# BP_MCU.net
KiCad netlist of a schematic drawn in EAGLE
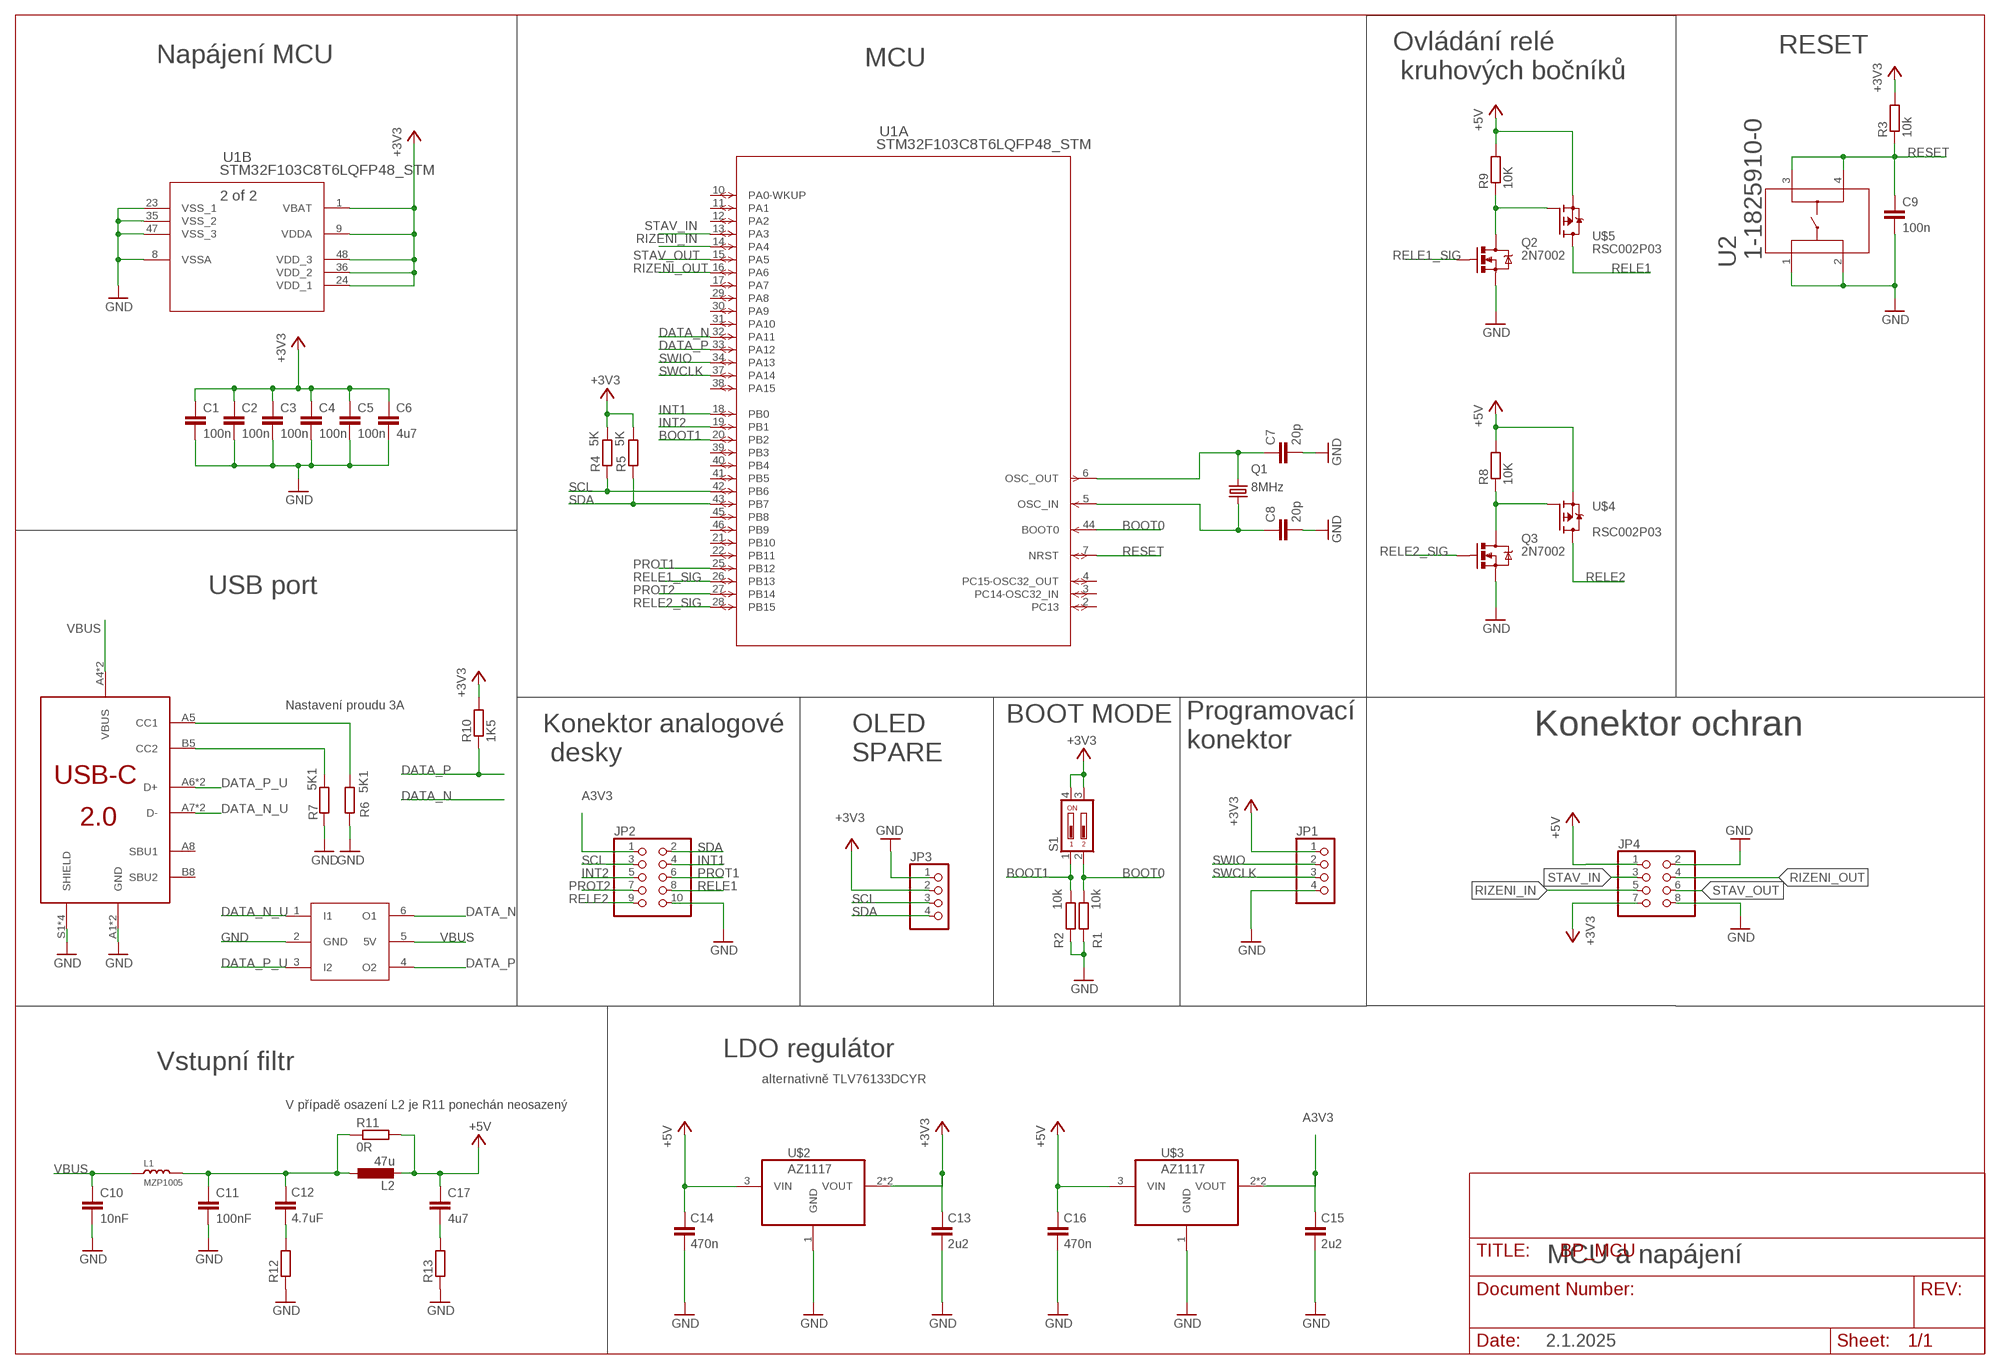
[diagram p0: schematic, sheet 1]

(export (version "E")
  (design (tool "Eeschema 10.0.6"))
  (components
    (comp (ref "C1")
      (value "100n")
      (footprint "eagle-import:C0805")
      (libsource (lib "eagle-import") (part "C-EUC0805"))
    )
    (comp (ref "C2")
      (value "100n")
      (footprint "eagle-import:C0805")
      (libsource (lib "eagle-import") (part "C-EUC0805"))
    )
    (comp (ref "C3")
      (value "100n")
      (footprint "eagle-import:C0805")
      (libsource (lib "eagle-import") (part "C-EUC0805"))
    )
    (comp (ref "C4")
      (value "100n")
      (footprint "eagle-import:C0805")
      (libsource (lib "eagle-import") (part "C-EUC0805"))
    )
    (comp (ref "C5")
      (value "100n")
      (footprint "eagle-import:C0805")
      (libsource (lib "eagle-import") (part "C-EUC0805"))
    )
    (comp (ref "C6")
      (value "4u7")
      (footprint "eagle-import:C0805")
      (libsource (lib "eagle-import") (part "C-EUC0805"))
    )
    (comp (ref "C7")
      (value "20p")
      (footprint "eagle-import:C0805")
      (libsource (lib "eagle-import") (part "C-EUC0805"))
    )
    (comp (ref "C8")
      (value "20p")
      (footprint "eagle-import:C0805")
      (libsource (lib "eagle-import") (part "C-EUC0805"))
    )
    (comp (ref "C9")
      (value "100n")
      (footprint "eagle-import:C0805")
      (libsource (lib "eagle-import") (part "C-EUC0805"))
    )
    (comp (ref "C10")
      (value "10nF")
      (footprint "eagle-import:C0805")
      (libsource (lib "eagle-import") (part "C-EUC0805"))
    )
    (comp (ref "C11")
      (value "100nF")
      (footprint "eagle-import:C0805")
      (libsource (lib "eagle-import") (part "resistor_348_C-EUC0805"))
    )
    (comp (ref "C12")
      (value "4.7uF")
      (footprint "eagle-import:C0805")
      (libsource (lib "eagle-import") (part "resistor_348_C-EUC0805"))
    )
    (comp (ref "C13")
      (value "2u2")
      (footprint "eagle-import:C0805")
      (libsource (lib "eagle-import") (part "C-EUC0805"))
    )
    (comp (ref "C14")
      (value "470n")
      (footprint "eagle-import:C0805")
      (libsource (lib "eagle-import") (part "C-EUC0805"))
    )
    (comp (ref "C15")
      (value "2u2")
      (footprint "eagle-import:C0805")
      (libsource (lib "eagle-import") (part "C-EUC0805"))
    )
    (comp (ref "C16")
      (value "470n")
      (footprint "eagle-import:C0805")
      (libsource (lib "eagle-import") (part "C-EUC0805"))
    )
    (comp (ref "C17")
      (value "4u7")
      (footprint "eagle-import:C0805")
      (libsource (lib "eagle-import") (part "C-EUC0805"))
    )
    (comp (ref "JP1")
      (value "PINHD-1X4")
      (footprint "eagle-import:1X04")
      (libsource (lib "eagle-import") (part "PINHD-1X4"))
    )
    (comp (ref "JP2")
      (value "PINHD-2X5")
      (footprint "eagle-import:2X05")
      (libsource (lib "eagle-import") (part "PINHD-2X5"))
    )
    (comp (ref "JP3")
      (value "PINHD-1X4")
      (footprint "eagle-import:1X04")
      (libsource (lib "eagle-import") (part "PINHD-1X4"))
    )
    (comp (ref "JP4")
      (value "PINHD-2X4")
      (footprint "eagle-import:2X04")
      (libsource (lib "eagle-import") (part "PINHD-2X4"))
    )
    (comp (ref "L1")
      (value "MZP1005")
      (footprint "eagle-import:INDUCTOR_L0402")
      (libsource (lib "eagle-import") (part "INDUCTOR_INDUCTOR/FERRITE-BEAD0402"))
    )
    (comp (ref "L2")
      (value "47u")
      (footprint "eagle-import:AMRM001")
      (libsource (lib "eagle-import") (part "AMRM00101040470MA1"))
    )
    (comp (ref "Q1")
      (value "8MHz")
      (footprint "eagle-import:HC49UP")
      (libsource (lib "eagle-import") (part "CRYSTALHC49UP"))
    )
    (comp (ref "Q2")
      (value "2N7002")
      (footprint "eagle-import:SOT323")
      (libsource (lib "eagle-import") (part "MOSFET-NCHANNEL2N7002PW"))
    )
    (comp (ref "Q3")
      (value "2N7002")
      (footprint "eagle-import:SOT323")
      (libsource (lib "eagle-import") (part "MOSFET-NCHANNEL2N7002PW"))
    )
    (comp (ref "R1")
      (value "10k")
      (footprint "eagle-import:R0805")
      (libsource (lib "eagle-import") (part "R-EU_R0805"))
    )
    (comp (ref "R2")
      (value "10k")
      (footprint "eagle-import:R0805")
      (libsource (lib "eagle-import") (part "R-EU_R0805"))
    )
    (comp (ref "R3")
      (value "10k")
      (footprint "eagle-import:R0805")
      (libsource (lib "eagle-import") (part "R-EU_R0805"))
    )
    (comp (ref "R4")
      (value "5K")
      (footprint "eagle-import:R0805")
      (libsource (lib "eagle-import") (part "R-EU_R0805"))
    )
    (comp (ref "R5")
      (value "5K")
      (footprint "eagle-import:R0805")
      (libsource (lib "eagle-import") (part "R-EU_R0805"))
    )
    (comp (ref "R6")
      (value "5K1")
      (footprint "eagle-import:R0805")
      (libsource (lib "eagle-import") (part "R-EU_R0805"))
    )
    (comp (ref "R7")
      (value "5K1")
      (footprint "eagle-import:R0805")
      (libsource (lib "eagle-import") (part "R-EU_R0805"))
    )
    (comp (ref "R8")
      (value "10K")
      (footprint "eagle-import:R0805")
      (libsource (lib "eagle-import") (part "R-EU_R0805"))
    )
    (comp (ref "R9")
      (value "10K")
      (footprint "eagle-import:R0805")
      (libsource (lib "eagle-import") (part "R-EU_R0805"))
    )
    (comp (ref "R10")
      (value "1K5")
      (footprint "eagle-import:R0805")
      (libsource (lib "eagle-import") (part "R-EU_R0805"))
    )
    (comp (ref "R11")
      (value "0R")
      (footprint "eagle-import:R0805")
      (libsource (lib "eagle-import") (part "R-EU_R0805"))
    )
    (comp (ref "R12")
      (value "R-EU_R0805")
      (footprint "eagle-import:R0805")
      (libsource (lib "eagle-import") (part "R-EU_R0805"))
    )
    (comp (ref "R13")
      (value "R-EU_R0805")
      (footprint "eagle-import:R0805")
      (libsource (lib "eagle-import") (part "R-EU_R0805"))
    )
    (comp (ref "S1")
      (value "SD4-02")
      (footprint "eagle-import:SD4-02")
      (libsource (lib "eagle-import") (part "SD4-02"))
    )
    (comp (ref "U$1")
      (value "217179-0001-USB-C")
      (footprint "eagle-import:TYPEC16")
      (libsource (lib "eagle-import") (part "217179-0001-USB-C"))
    )
    (comp (ref "U$2")
      (value "AZ1117")
      (footprint "eagle-import:SOT230P700X180-4N")
      (libsource (lib "eagle-import") (part "AZ1117"))
    )
    (comp (ref "U$3")
      (value "AZ1117")
      (footprint "eagle-import:SOT230P700X180-4N")
      (libsource (lib "eagle-import") (part "AZ1117"))
    )
    (comp (ref "U$4")
      (value "RSC002P03")
      (footprint "eagle-import:SOT95")
      (libsource (lib "eagle-import") (part "RSC002P03"))
    )
    (comp (ref "U$5")
      (value "RSC002P03")
      (footprint "eagle-import:SOT95")
      (libsource (lib "eagle-import") (part "RSC002P03"))
    )
    (comp (ref "U$6")
      (value "USBLC6-2")
      (footprint "eagle-import:SOT23-6L")
      (libsource (lib "eagle-import") (part "USBLC6-2"))
    )
    (comp (ref "U1")
      (value "STM32F103C8T6LQFP48_STM")
      (footprint "eagle-import:LQFP48_STM")
      (fields
        (field (name "MANUFACTURER_PART_NUMBER") "STM32F103C8T6")
        (field (name "COPYRIGHT") "Copyright (C) 2024 Ultra Librarian. All rights reserved.")
      )
      (libsource (lib "eagle-import") (part "STM32F103C8T6LQFP48_STM"))
    )
    (comp (ref "U2")
      (value "1-1825910-0")
      (footprint "eagle-import:SWITCH_1-1825910-0")
      (fields (field (name "COPYRIGHT") "Copyright (C) 2016 Accelerated Designs. All rights reserved"))
      (libsource (lib "eagle-import") (part "1-1825910-0"))
    )
  )
  (nets
    (net (code "1") (name "+3V3") (class "Default")
      (node (ref "C1") (pin "1") (pinfunction "1_1") (pintype "passive"))
      (node (ref "C13") (pin "1") (pinfunction "1_1") (pintype "passive"))
      (node (ref "C2") (pin "1") (pinfunction "1_1") (pintype "passive"))
      (node (ref "C3") (pin "1") (pinfunction "1_1") (pintype "passive"))
      (node (ref "C4") (pin "1") (pinfunction "1_1") (pintype "passive"))
      (node (ref "C5") (pin "1") (pinfunction "1_1") (pintype "passive"))
      (node (ref "C6") (pin "1") (pinfunction "1_1") (pintype "passive"))
      (node (ref "JP1") (pin "1") (pinfunction "1_1") (pintype "passive"))
      (node (ref "JP3") (pin "2") (pinfunction "2_2") (pintype "passive"))
      (node (ref "JP4") (pin "7") (pinfunction "7_7") (pintype "passive"))
      (node (ref "R10") (pin "2") (pinfunction "2_2") (pintype "passive"))
      (node (ref "R3") (pin "2") (pinfunction "2_2") (pintype "passive"))
      (node (ref "R4") (pin "2") (pinfunction "2_2") (pintype "passive"))
      (node (ref "R5") (pin "2") (pinfunction "2_2") (pintype "passive"))
      (node (ref "S1") (pin "3") (pinfunction "3_3") (pintype "passive"))
      (node (ref "S1") (pin "4") (pinfunction "4_4") (pintype "passive"))
      (node (ref "U$2") (pin "2") (pinfunction "VOUT_2") (pintype "output"))
      (node (ref "U$2") (pin "4") (pinfunction "VOUT_4") (pintype "output"))
      (node (ref "U1") (pin "1") (pinfunction "VBAT_1") (pintype "power_in"))
      (node (ref "U1") (pin "24") (pinfunction "VDD_1_24") (pintype "power_in"))
      (node (ref "U1") (pin "36") (pinfunction "VDD_2_36") (pintype "power_in"))
      (node (ref "U1") (pin "48") (pinfunction "VDD_3_48") (pintype "power_in"))
      (node (ref "U1") (pin "9") (pinfunction "VDDA_9") (pintype "power_in"))
    )
    (net (code "2") (name "+5V") (class "Default")
      (node (ref "C14") (pin "1") (pinfunction "1_1") (pintype "passive"))
      (node (ref "C16") (pin "1") (pinfunction "1_1") (pintype "passive"))
      (node (ref "C17") (pin "1") (pinfunction "1_1") (pintype "passive"))
      (node (ref "JP4") (pin "1") (pinfunction "1_1") (pintype "passive"))
      (node (ref "L2") (pin "P$2") (pinfunction "2_P$2") (pintype "passive"))
      (node (ref "R11") (pin "2") (pinfunction "2_2") (pintype "passive"))
      (node (ref "R8") (pin "2") (pinfunction "2_2") (pintype "passive"))
      (node (ref "R9") (pin "2") (pinfunction "2_2") (pintype "passive"))
      (node (ref "U$2") (pin "3") (pinfunction "VIN_3") (pintype "input"))
      (node (ref "U$3") (pin "3") (pinfunction "VIN_3") (pintype "input"))
      (node (ref "U$4") (pin "1") (pinfunction "S_1") (pintype "passive"))
      (node (ref "U$5") (pin "1") (pinfunction "S_1") (pintype "passive"))
    )
    (net (code "3") (name "/A3V3") (class "Default")
      (node (ref "C15") (pin "1") (pinfunction "1_1") (pintype "passive"))
      (node (ref "JP2") (pin "1") (pinfunction "1_1") (pintype "passive"))
      (node (ref "U$3") (pin "2") (pinfunction "VOUT_2") (pintype "output"))
      (node (ref "U$3") (pin "4") (pinfunction "VOUT_4") (pintype "output"))
    )
    (net (code "4") (name "/BOOT0") (class "Default")
      (node (ref "R1") (pin "2") (pinfunction "2_2") (pintype "passive"))
      (node (ref "S1") (pin "2") (pinfunction "2_2") (pintype "passive"))
      (node (ref "U1") (pin "44") (pinfunction "BOOT0_44") (pintype "input"))
    )
    (net (code "5") (name "/BOOT1") (class "Default")
      (node (ref "R2") (pin "2") (pinfunction "2_2") (pintype "passive"))
      (node (ref "S1") (pin "1") (pinfunction "1_1") (pintype "passive"))
      (node (ref "U1") (pin "20") (pinfunction "PB2_20") (pintype "bidirectional"))
    )
    (net (code "6") (name "/DATA_N") (class "Default")
      (node (ref "U$6") (pin "6") (pinfunction "O1_6") (pintype "bidirectional"))
      (node (ref "U1") (pin "32") (pinfunction "PA11_32") (pintype "bidirectional"))
    )
    (net (code "7") (name "/DATA_N_U") (class "Default")
      (node (ref "U$1") (pin "A7") (pinfunction "D-_A7") (pintype "bidirectional"))
      (node (ref "U$1") (pin "B7") (pinfunction "D-_B7") (pintype "bidirectional"))
      (node (ref "U$6") (pin "1") (pinfunction "I1_1") (pintype "bidirectional"))
    )
    (net (code "8") (name "/DATA_P") (class "Default")
      (node (ref "R10") (pin "1") (pinfunction "1_1") (pintype "passive"))
      (node (ref "U$6") (pin "4") (pinfunction "O2_4") (pintype "bidirectional"))
      (node (ref "U1") (pin "33") (pinfunction "PA12_33") (pintype "bidirectional"))
    )
    (net (code "9") (name "/DATA_P_U") (class "Default")
      (node (ref "U$1") (pin "A6") (pinfunction "D+_A6") (pintype "bidirectional"))
      (node (ref "U$1") (pin "B6") (pinfunction "D+_B6") (pintype "bidirectional"))
      (node (ref "U$6") (pin "3") (pinfunction "I2_3") (pintype "bidirectional"))
    )
    (net (code "10") (name "/INT1") (class "Default")
      (node (ref "JP2") (pin "4") (pinfunction "4_4") (pintype "passive"))
      (node (ref "U1") (pin "18") (pinfunction "PB0_18") (pintype "bidirectional"))
    )
    (net (code "11") (name "/INT2") (class "Default")
      (node (ref "JP2") (pin "5") (pinfunction "5_5") (pintype "passive"))
      (node (ref "U1") (pin "19") (pinfunction "PB1_19") (pintype "bidirectional"))
    )
    (net (code "12") (name "/PROT1") (class "Default")
      (node (ref "JP2") (pin "6") (pinfunction "6_6") (pintype "passive"))
      (node (ref "U1") (pin "25") (pinfunction "PB12_25") (pintype "bidirectional"))
    )
    (net (code "13") (name "/PROT2") (class "Default")
      (node (ref "JP2") (pin "7") (pinfunction "7_7") (pintype "passive"))
      (node (ref "U1") (pin "27") (pinfunction "PB14_27") (pintype "bidirectional"))
    )
    (net (code "14") (name "/RELE1") (class "Default")
      (node (ref "JP2") (pin "8") (pinfunction "8_8") (pintype "passive"))
      (node (ref "U$5") (pin "3") (pinfunction "D_3") (pintype "passive"))
    )
    (net (code "15") (name "/RELE1_SIG") (class "Default")
      (node (ref "Q2") (pin "1") (pinfunction "G_1") (pintype "passive"))
      (node (ref "U1") (pin "26") (pinfunction "PB13_26") (pintype "bidirectional"))
    )
    (net (code "16") (name "/RELE2") (class "Default")
      (node (ref "JP2") (pin "9") (pinfunction "9_9") (pintype "passive"))
      (node (ref "U$4") (pin "3") (pinfunction "D_3") (pintype "passive"))
    )
    (net (code "17") (name "/RELE2_SIG") (class "Default")
      (node (ref "Q3") (pin "1") (pinfunction "G_1") (pintype "passive"))
      (node (ref "U1") (pin "28") (pinfunction "PB15_28") (pintype "bidirectional"))
    )
    (net (code "18") (name "/RESET") (class "Default")
      (node (ref "C9") (pin "1") (pinfunction "1_1") (pintype "passive"))
      (node (ref "R3") (pin "1") (pinfunction "1_1") (pintype "passive"))
      (node (ref "U1") (pin "7") (pinfunction "NRST_7") (pintype "bidirectional"))
      (node (ref "U2") (pin "3") (pinfunction "3_3") (pintype "passive"))
      (node (ref "U2") (pin "4") (pinfunction "4_4") (pintype "passive"))
    )
    (net (code "19") (name "/SCL") (class "Default")
      (node (ref "JP2") (pin "3") (pinfunction "3_3") (pintype "passive"))
      (node (ref "JP3") (pin "3") (pinfunction "3_3") (pintype "passive"))
      (node (ref "R4") (pin "1") (pinfunction "1_1") (pintype "passive"))
      (node (ref "U1") (pin "42") (pinfunction "PB6_42") (pintype "bidirectional"))
    )
    (net (code "20") (name "/SDA") (class "Default")
      (node (ref "JP2") (pin "2") (pinfunction "2_2") (pintype "passive"))
      (node (ref "JP3") (pin "4") (pinfunction "4_4") (pintype "passive"))
      (node (ref "R5") (pin "1") (pinfunction "1_1") (pintype "passive"))
      (node (ref "U1") (pin "43") (pinfunction "PB7_43") (pintype "bidirectional"))
    )
    (net (code "21") (name "/SWCLK") (class "Default")
      (node (ref "JP1") (pin "3") (pinfunction "3_3") (pintype "passive"))
      (node (ref "U1") (pin "37") (pinfunction "PA14_37") (pintype "bidirectional"))
    )
    (net (code "22") (name "/SWIO") (class "Default")
      (node (ref "JP1") (pin "2") (pinfunction "2_2") (pintype "passive"))
      (node (ref "U1") (pin "34") (pinfunction "PA13_34") (pintype "bidirectional"))
    )
    (net (code "23") (name "/VBUS") (class "Default")
      (node (ref "C10") (pin "1") (pinfunction "1_1") (pintype "passive"))
      (node (ref "L1") (pin "1") (pinfunction "1_1") (pintype "passive"))
      (node (ref "U$1") (pin "A4") (pinfunction "VBUS_A4") (pintype "bidirectional"))
      (node (ref "U$1") (pin "A9") (pinfunction "VBUS_A9") (pintype "bidirectional"))
      (node (ref "U$6") (pin "5") (pinfunction "5V_5") (pintype "bidirectional"))
    )
    (net (code "24") (name "GND") (class "Default")
      (node (ref "C1") (pin "2") (pinfunction "2_2") (pintype "passive"))
      (node (ref "C10") (pin "2") (pinfunction "2_2") (pintype "passive"))
      (node (ref "C11") (pin "2") (pinfunction "2_2") (pintype "passive"))
      (node (ref "C13") (pin "2") (pinfunction "2_2") (pintype "passive"))
      (node (ref "C14") (pin "2") (pinfunction "2_2") (pintype "passive"))
      (node (ref "C15") (pin "2") (pinfunction "2_2") (pintype "passive"))
      (node (ref "C16") (pin "2") (pinfunction "2_2") (pintype "passive"))
      (node (ref "C2") (pin "2") (pinfunction "2_2") (pintype "passive"))
      (node (ref "C3") (pin "2") (pinfunction "2_2") (pintype "passive"))
      (node (ref "C4") (pin "2") (pinfunction "2_2") (pintype "passive"))
      (node (ref "C5") (pin "2") (pinfunction "2_2") (pintype "passive"))
      (node (ref "C6") (pin "2") (pinfunction "2_2") (pintype "passive"))
      (node (ref "C7") (pin "2") (pinfunction "2_2") (pintype "passive"))
      (node (ref "C8") (pin "2") (pinfunction "2_2") (pintype "passive"))
      (node (ref "C9") (pin "2") (pinfunction "2_2") (pintype "passive"))
      (node (ref "JP1") (pin "4") (pinfunction "4_4") (pintype "passive"))
      (node (ref "JP2") (pin "10") (pinfunction "10_10") (pintype "passive"))
      (node (ref "JP3") (pin "1") (pinfunction "1_1") (pintype "passive"))
      (node (ref "JP4") (pin "2") (pinfunction "2_2") (pintype "passive"))
      (node (ref "JP4") (pin "8") (pinfunction "8_8") (pintype "passive"))
      (node (ref "Q2") (pin "2") (pinfunction "S_2") (pintype "passive"))
      (node (ref "Q3") (pin "2") (pinfunction "S_2") (pintype "passive"))
      (node (ref "R1") (pin "1") (pinfunction "1_1") (pintype "passive"))
      (node (ref "R12") (pin "1") (pinfunction "1_1") (pintype "passive"))
      (node (ref "R13") (pin "1") (pinfunction "1_1") (pintype "passive"))
      (node (ref "R2") (pin "1") (pinfunction "1_1") (pintype "passive"))
      (node (ref "R6") (pin "2") (pinfunction "2_2") (pintype "passive"))
      (node (ref "R7") (pin "2") (pinfunction "2_2") (pintype "passive"))
      (node (ref "U$1") (pin "A1") (pinfunction "GND_A1") (pintype "bidirectional"))
      (node (ref "U$1") (pin "A12") (pinfunction "GND_A12") (pintype "bidirectional"))
      (node (ref "U$1") (pin "S1") (pinfunction "SHIELD_S1") (pintype "bidirectional"))
      (node (ref "U$1") (pin "S2") (pinfunction "SHIELD_S2") (pintype "bidirectional"))
      (node (ref "U$1") (pin "S3") (pinfunction "SHIELD_S3") (pintype "bidirectional"))
      (node (ref "U$1") (pin "S4") (pinfunction "SHIELD_S4") (pintype "bidirectional"))
      (node (ref "U$2") (pin "1") (pinfunction "GND_1") (pintype "power_in"))
      (node (ref "U$3") (pin "1") (pinfunction "GND_1") (pintype "power_in"))
      (node (ref "U$6") (pin "2") (pinfunction "GND_2") (pintype "bidirectional"))
      (node (ref "U1") (pin "23") (pinfunction "VSS_1_23") (pintype "power_in"))
      (node (ref "U1") (pin "35") (pinfunction "VSS_2_35") (pintype "power_in"))
      (node (ref "U1") (pin "47") (pinfunction "VSS_3_47") (pintype "power_in"))
      (node (ref "U1") (pin "8") (pinfunction "VSSA_8") (pintype "power_in"))
      (node (ref "U2") (pin "1") (pinfunction "1_1") (pintype "passive"))
      (node (ref "U2") (pin "2") (pinfunction "2_2") (pintype "passive"))
    )
    (net (code "25") (name "Net-(C12-Pad2)") (class "Default")
      (node (ref "C12") (pin "2") (pinfunction "2_2") (pintype "passive"))
      (node (ref "R12") (pin "2") (pinfunction "2_2") (pintype "passive"))
    )
    (net (code "26") (name "Net-(C17-Pad2)") (class "Default")
      (node (ref "C17") (pin "2") (pinfunction "2_2") (pintype "passive"))
      (node (ref "R13") (pin "2") (pinfunction "2_2") (pintype "passive"))
    )
    (net (code "27") (name "Net-(L2-1)") (class "Default")
      (node (ref "C11") (pin "1") (pinfunction "1_1") (pintype "passive"))
      (node (ref "C12") (pin "1") (pinfunction "1_1") (pintype "passive"))
      (node (ref "L1") (pin "2") (pinfunction "2_2") (pintype "passive"))
      (node (ref "L2") (pin "P$1") (pinfunction "1_P$1") (pintype "passive"))
      (node (ref "R11") (pin "1") (pinfunction "1_1") (pintype "passive"))
    )
    (net (code "28") (name "Net-(Q2-D)") (class "Default")
      (node (ref "Q2") (pin "3") (pinfunction "D_3") (pintype "passive"))
      (node (ref "R9") (pin "1") (pinfunction "1_1") (pintype "passive"))
      (node (ref "U$5") (pin "2") (pinfunction "G_2") (pintype "passive"))
    )
    (net (code "29") (name "Net-(Q3-D)") (class "Default")
      (node (ref "Q3") (pin "3") (pinfunction "D_3") (pintype "passive"))
      (node (ref "R8") (pin "1") (pinfunction "1_1") (pintype "passive"))
      (node (ref "U$4") (pin "2") (pinfunction "G_2") (pintype "passive"))
    )
    (net (code "30") (name "Net-(U$1-CC1)") (class "Default")
      (node (ref "R6") (pin "1") (pinfunction "1_1") (pintype "passive"))
      (node (ref "U$1") (pin "A5") (pinfunction "CC1_A5") (pintype "bidirectional"))
    )
    (net (code "31") (name "Net-(U$1-CC2)") (class "Default")
      (node (ref "R7") (pin "1") (pinfunction "1_1") (pintype "passive"))
      (node (ref "U$1") (pin "B5") (pinfunction "CC2_B5") (pintype "bidirectional"))
    )
    (net (code "32") (name "Net-(U1A-OSC_IN)") (class "Default")
      (node (ref "C8") (pin "1") (pinfunction "1_1") (pintype "passive"))
      (node (ref "Q1") (pin "1") (pinfunction "1_1") (pintype "passive"))
      (node (ref "U1") (pin "5") (pinfunction "OSC_IN_5") (pintype "input"))
    )
    (net (code "33") (name "Net-(U1A-OSC_OUT)") (class "Default")
      (node (ref "C7") (pin "1") (pinfunction "1_1") (pintype "passive"))
      (node (ref "Q1") (pin "2") (pinfunction "2_2") (pintype "passive"))
      (node (ref "U1") (pin "6") (pinfunction "OSC_OUT_6") (pintype "output"))
    )
    (net (code "34") (name "RIZENI_IN") (class "Default")
      (node (ref "JP4") (pin "5") (pinfunction "5_5") (pintype "passive"))
      (node (ref "U1") (pin "14") (pinfunction "PA4_14") (pintype "bidirectional"))
    )
    (net (code "35") (name "RIZENI_OUT") (class "Default")
      (node (ref "JP4") (pin "4") (pinfunction "4_4") (pintype "passive"))
      (node (ref "U1") (pin "16") (pinfunction "PA6_16") (pintype "bidirectional"))
    )
    (net (code "36") (name "STAV_IN") (class "Default")
      (node (ref "JP4") (pin "3") (pinfunction "3_3") (pintype "passive"))
      (node (ref "U1") (pin "13") (pinfunction "PA3_13") (pintype "bidirectional"))
    )
    (net (code "37") (name "STAV_OUT") (class "Default")
      (node (ref "JP4") (pin "6") (pinfunction "6_6") (pintype "passive"))
      (node (ref "U1") (pin "15") (pinfunction "PA5_15") (pintype "bidirectional"))
    )
    (net (code "38") (name "unconnected-(U$1-SBU1-PadA8)") (class "Default")
      (node (ref "U$1") (pin "A8") (pinfunction "SBU1_A8") (pintype "bidirectional"))
    )
    (net (code "39") (name "unconnected-(U$1-SBU2-PadB8)") (class "Default")
      (node (ref "U$1") (pin "B8") (pinfunction "SBU2_B8") (pintype "bidirectional"))
    )
    (net (code "40") (name "unconnected-(U1A-PA0-WKUP-Pad10)") (class "Default")
      (node (ref "U1") (pin "10") (pinfunction "PA0-WKUP_10") (pintype "bidirectional"))
    )
    (net (code "41") (name "unconnected-(U1A-PA1-Pad11)") (class "Default")
      (node (ref "U1") (pin "11") (pinfunction "PA1_11") (pintype "bidirectional"))
    )
    (net (code "42") (name "unconnected-(U1A-PA2-Pad12)") (class "Default")
      (node (ref "U1") (pin "12") (pinfunction "PA2_12") (pintype "bidirectional"))
    )
    (net (code "43") (name "unconnected-(U1A-PA7-Pad17)") (class "Default")
      (node (ref "U1") (pin "17") (pinfunction "PA7_17") (pintype "bidirectional"))
    )
    (net (code "44") (name "unconnected-(U1A-PA8-Pad29)") (class "Default")
      (node (ref "U1") (pin "29") (pinfunction "PA8_29") (pintype "bidirectional"))
    )
    (net (code "45") (name "unconnected-(U1A-PA9-Pad30)") (class "Default")
      (node (ref "U1") (pin "30") (pinfunction "PA9_30") (pintype "bidirectional"))
    )
    (net (code "46") (name "unconnected-(U1A-PA10-Pad31)") (class "Default")
      (node (ref "U1") (pin "31") (pinfunction "PA10_31") (pintype "bidirectional"))
    )
    (net (code "47") (name "unconnected-(U1A-PA15-Pad38)") (class "Default")
      (node (ref "U1") (pin "38") (pinfunction "PA15_38") (pintype "bidirectional"))
    )
    (net (code "48") (name "unconnected-(U1A-PB3-Pad39)") (class "Default")
      (node (ref "U1") (pin "39") (pinfunction "PB3_39") (pintype "bidirectional"))
    )
    (net (code "49") (name "unconnected-(U1A-PB4-Pad40)") (class "Default")
      (node (ref "U1") (pin "40") (pinfunction "PB4_40") (pintype "bidirectional"))
    )
    (net (code "50") (name "unconnected-(U1A-PB5-Pad41)") (class "Default")
      (node (ref "U1") (pin "41") (pinfunction "PB5_41") (pintype "bidirectional"))
    )
    (net (code "51") (name "unconnected-(U1A-PB8-Pad45)") (class "Default")
      (node (ref "U1") (pin "45") (pinfunction "PB8_45") (pintype "bidirectional"))
    )
    (net (code "52") (name "unconnected-(U1A-PB9-Pad46)") (class "Default")
      (node (ref "U1") (pin "46") (pinfunction "PB9_46") (pintype "bidirectional"))
    )
    (net (code "53") (name "unconnected-(U1A-PB10-Pad21)") (class "Default")
      (node (ref "U1") (pin "21") (pinfunction "PB10_21") (pintype "bidirectional"))
    )
    (net (code "54") (name "unconnected-(U1A-PB11-Pad22)") (class "Default")
      (node (ref "U1") (pin "22") (pinfunction "PB11_22") (pintype "bidirectional"))
    )
    (net (code "55") (name "unconnected-(U1A-PC13-Pad2)") (class "Default")
      (node (ref "U1") (pin "2") (pinfunction "PC13_2") (pintype "bidirectional"))
    )
    (net (code "56") (name "unconnected-(U1A-PC14-OSC32_IN-Pad3)") (class "Default")
      (node (ref "U1") (pin "3") (pinfunction "PC14-OSC32_IN_3") (pintype "bidirectional"))
    )
    (net (code "57") (name "unconnected-(U1A-PC15-OSC32_OUT-Pad4)") (class "Default")
      (node (ref "U1") (pin "4") (pinfunction "PC15-OSC32_OUT_4") (pintype "bidirectional"))
    )
  )
)
